# CW521_BallisticGel_Connectors.net
KiCad netlist of a schematic drawn in Altium Designer
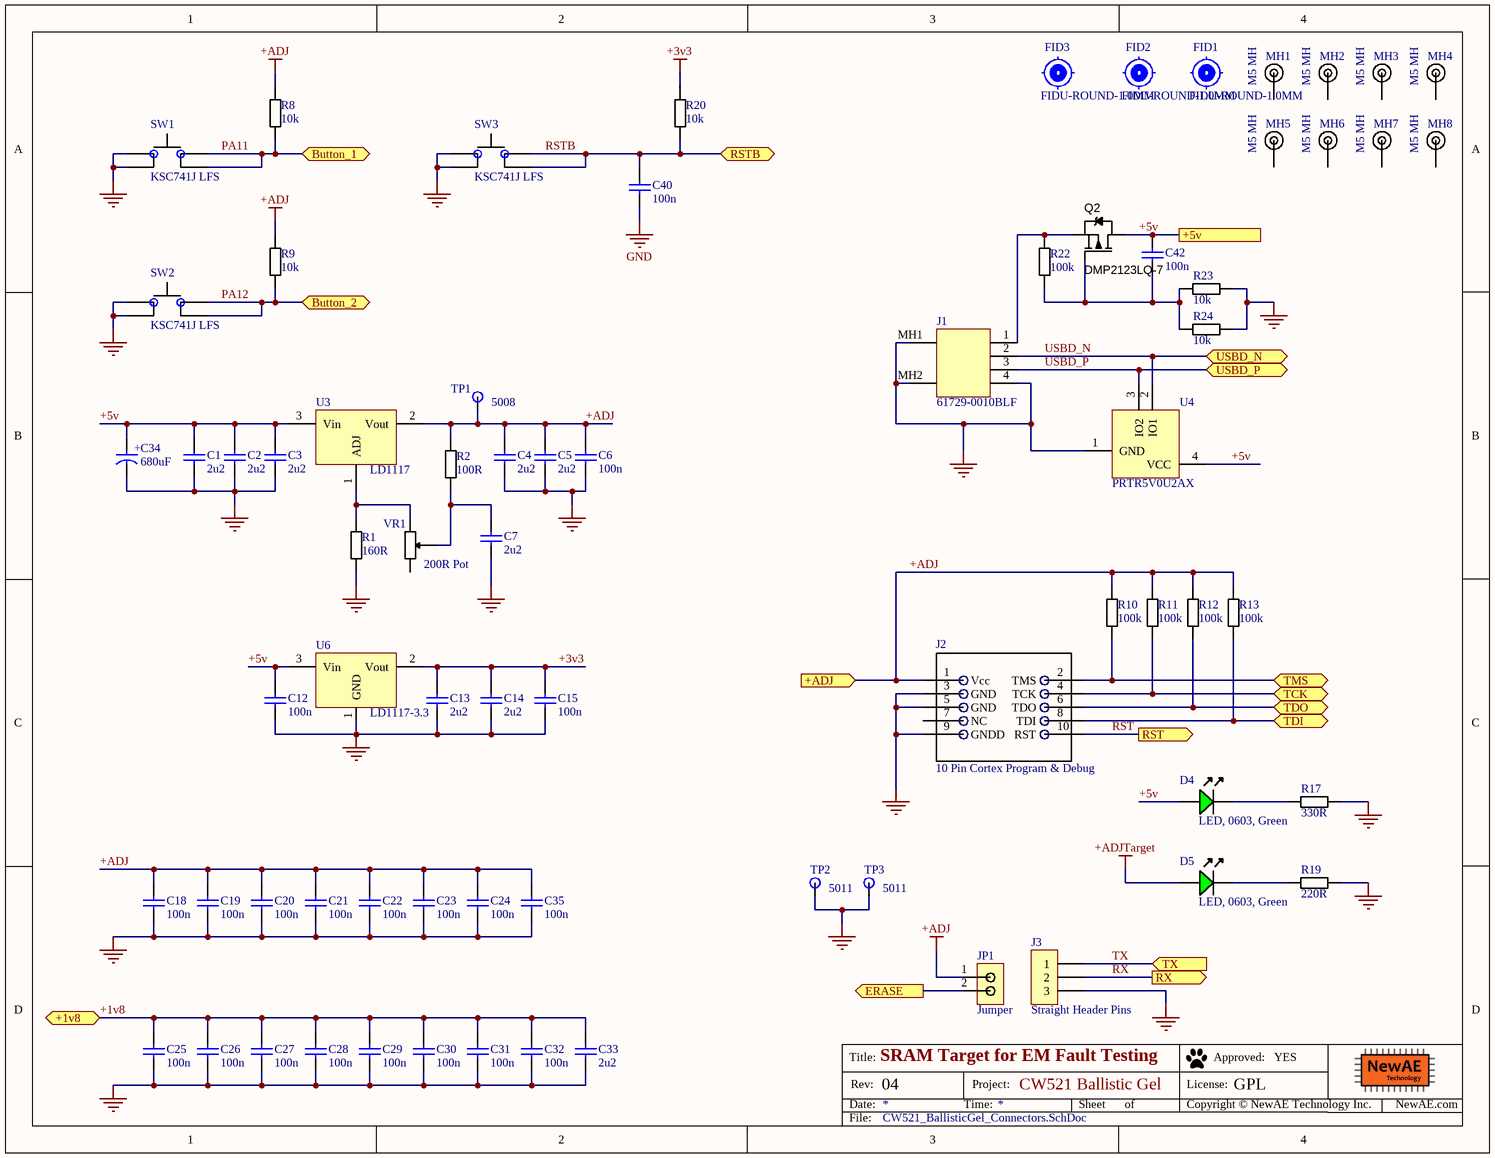
[diagram p0: CW521_BallisticGel_Connectors.SchDoc]

(export (version "E")
  (design (tool "Eeschema 10.0.6"))
  (components
    (comp (ref "C1")
      (value "2u2")
      (footprint "CAPC0603_M")
      (description "2u2, 0603")
      (fields (field (name "PART NUMBER") "CCHIP-2u2-0603"))
      (libsource (lib "NewAE_AltiumLib") (part "CAP"))
    )
    (comp (ref "C2")
      (value "2u2")
      (footprint "CAPC0603_M")
      (description "2u2, 0603")
      (fields (field (name "PART NUMBER") "CCHIP-2u2-0603"))
      (libsource (lib "NewAE_AltiumLib") (part "CAP"))
    )
    (comp (ref "C3")
      (value "2u2")
      (footprint "CAPC0603_M")
      (description "2u2, 0603")
      (fields (field (name "PART NUMBER") "CCHIP-2u2-0603"))
      (libsource (lib "NewAE_AltiumLib") (part "CAP"))
    )
    (comp (ref "C4")
      (value "2u2")
      (footprint "CAPC0603_M")
      (description "2u2, 0603")
      (fields (field (name "PART NUMBER") "CCHIP-2u2-0603"))
      (libsource (lib "NewAE_AltiumLib") (part "CAP"))
    )
    (comp (ref "C5")
      (value "2u2")
      (footprint "CAPC0603_M")
      (description "2u2, 0603")
      (fields (field (name "PART NUMBER") "CCHIP-2u2-0603"))
      (libsource (lib "NewAE_AltiumLib") (part "CAP"))
    )
    (comp (ref "C6")
      (value "100n")
      (footprint "CAPC0603_M")
      (description "100n, 0603")
      (fields (field (name "PART NUMBER") "CCHIP-100n-0603"))
      (libsource (lib "NewAE_AltiumLib") (part "CAP"))
    )
    (comp (ref "C7")
      (value "2u2")
      (footprint "CAPC0603_M")
      (description "2u2, 0603")
      (fields (field (name "PART NUMBER") "CCHIP-2u2-0603"))
      (libsource (lib "NewAE_AltiumLib") (part "CAP"))
    )
    (comp (ref "C12")
      (value "100n")
      (footprint "CAPC0603_M")
      (description "100n, 0603")
      (fields (field (name "PART NUMBER") "CCHIP-100n-0603"))
      (libsource (lib "NewAE_AltiumLib") (part "CAP"))
    )
    (comp (ref "C13")
      (value "2u2")
      (footprint "CAPC0603_M")
      (description "2u2, 0603")
      (fields (field (name "PART NUMBER") "CCHIP-2u2-0603"))
      (libsource (lib "NewAE_AltiumLib") (part "CAP"))
    )
    (comp (ref "C14")
      (value "2u2")
      (footprint "CAPC0603_M")
      (description "2u2, 0603")
      (fields (field (name "PART NUMBER") "CCHIP-2u2-0603"))
      (libsource (lib "NewAE_AltiumLib") (part "CAP"))
    )
    (comp (ref "C15")
      (value "100n")
      (footprint "CAPC0603_M")
      (description "100n, 0603")
      (fields (field (name "PART NUMBER") "CCHIP-100n-0603"))
      (libsource (lib "NewAE_AltiumLib") (part "CAP"))
    )
    (comp (ref "C18")
      (value "100n")
      (footprint "CAPC0603_M")
      (description "100n, 0603")
      (fields (field (name "PART NUMBER") "CCHIP-100n-0603"))
      (libsource (lib "NewAE_AltiumLib") (part "CAP"))
    )
    (comp (ref "C19")
      (value "100n")
      (footprint "CAPC0603_M")
      (description "100n, 0603")
      (fields (field (name "PART NUMBER") "CCHIP-100n-0603"))
      (libsource (lib "NewAE_AltiumLib") (part "CAP"))
    )
    (comp (ref "C20")
      (value "100n")
      (footprint "CAPC0603_M")
      (description "100n, 0603")
      (fields (field (name "PART NUMBER") "CCHIP-100n-0603"))
      (libsource (lib "NewAE_AltiumLib") (part "CAP"))
    )
    (comp (ref "C21")
      (value "100n")
      (footprint "CAPC0603_M")
      (description "100n, 0603")
      (fields (field (name "PART NUMBER") "CCHIP-100n-0603"))
      (libsource (lib "NewAE_AltiumLib") (part "CAP"))
    )
    (comp (ref "C22")
      (value "100n")
      (footprint "CAPC0603_M")
      (description "100n, 0603")
      (fields (field (name "PART NUMBER") "CCHIP-100n-0603"))
      (libsource (lib "NewAE_AltiumLib") (part "CAP"))
    )
    (comp (ref "C23")
      (value "100n")
      (footprint "CAPC0603_M")
      (description "100n, 0603")
      (fields (field (name "PART NUMBER") "CCHIP-100n-0603"))
      (libsource (lib "NewAE_AltiumLib") (part "CAP"))
    )
    (comp (ref "C24")
      (value "100n")
      (footprint "CAPC0603_M")
      (description "100n, 0603")
      (fields (field (name "PART NUMBER") "CCHIP-100n-0603"))
      (libsource (lib "NewAE_AltiumLib") (part "CAP"))
    )
    (comp (ref "C25")
      (value "100n")
      (footprint "CAPC0603_M")
      (description "100n, 0603")
      (fields (field (name "PART NUMBER") "CCHIP-100n-0603"))
      (libsource (lib "NewAE_AltiumLib") (part "CAP"))
    )
    (comp (ref "C26")
      (value "100n")
      (footprint "CAPC0603_M")
      (description "100n, 0603")
      (fields (field (name "PART NUMBER") "CCHIP-100n-0603"))
      (libsource (lib "NewAE_AltiumLib") (part "CAP"))
    )
    (comp (ref "C27")
      (value "100n")
      (footprint "CAPC0603_M")
      (description "100n, 0603")
      (fields (field (name "PART NUMBER") "CCHIP-100n-0603"))
      (libsource (lib "NewAE_AltiumLib") (part "CAP"))
    )
    (comp (ref "C28")
      (value "100n")
      (footprint "CAPC0603_M")
      (description "100n, 0603")
      (fields (field (name "PART NUMBER") "CCHIP-100n-0603"))
      (libsource (lib "NewAE_AltiumLib") (part "CAP"))
    )
    (comp (ref "C29")
      (value "100n")
      (footprint "CAPC0603_M")
      (description "100n, 0603")
      (fields (field (name "PART NUMBER") "CCHIP-100n-0603"))
      (libsource (lib "NewAE_AltiumLib") (part "CAP"))
    )
    (comp (ref "C30")
      (value "100n")
      (footprint "CAPC0603_M")
      (description "100n, 0603")
      (fields (field (name "PART NUMBER") "CCHIP-100n-0603"))
      (libsource (lib "NewAE_AltiumLib") (part "CAP"))
    )
    (comp (ref "C31")
      (value "100n")
      (footprint "CAPC0603_M")
      (description "100n, 0603")
      (fields (field (name "PART NUMBER") "CCHIP-100n-0603"))
      (libsource (lib "NewAE_AltiumLib") (part "CAP"))
    )
    (comp (ref "C32")
      (value "100n")
      (footprint "CAPC0603_M")
      (description "100n, 0603")
      (fields (field (name "PART NUMBER") "CCHIP-100n-0603"))
      (libsource (lib "NewAE_AltiumLib") (part "CAP"))
    )
    (comp (ref "C33")
      (value "2u2")
      (footprint "CAPC0603_M")
      (description "2u2, 0603")
      (fields (field (name "PART NUMBER") "CCHIP-2u2-0603"))
      (libsource (lib "NewAE_AltiumLib") (part "CAP"))
    )
    (comp (ref "C34")
      (value "680uF")
      (footprint "Cap_16v_680uF")
      (description "Aluminum electrolytic 680uF, 8x16mm, radial")
      (fields (field (name "PART NUMBER") "Cap_16v_680uF"))
      (libsource (lib "NewAE_AltiumLib") (part "CAP_POL"))
    )
    (comp (ref "C35")
      (value "100n")
      (footprint "CAPC0603_M")
      (description "100n, 0603")
      (fields (field (name "PART NUMBER") "CCHIP-100n-0603"))
      (libsource (lib "NewAE_AltiumLib") (part "CAP"))
    )
    (comp (ref "C40")
      (value "100n")
      (footprint "CAPC0603_M")
      (description "100n, 0603")
      (fields (field (name "PART NUMBER") "CCHIP-100n-0603"))
      (libsource (lib "NewAE_AltiumLib") (part "CAP"))
    )
    (comp (ref "C42")
      (value "100n")
      (footprint "CAPC0603_M")
      (description "100n, 0603")
      (fields (field (name "PART NUMBER") "CCHIP-100n-0603"))
      (libsource (lib "NewAE_AltiumLib") (part "CAP"))
    )
    (comp (ref "D4")
      (value "LED, 0603, Green")
      (footprint "LED-0603-GREEN")
      (description "Chip LED, Green")
      (fields (field (name "PART NUMBER") "LEDCHIP_0603_GREEN"))
      (libsource (lib "NewAE_AltiumLib") (part "LED_GREEN"))
    )
    (comp (ref "D5")
      (value "LED, 0603, Green")
      (footprint "LED-0603-GREEN")
      (description "Chip LED, Green")
      (fields (field (name "PART NUMBER") "LEDCHIP_0603_GREEN"))
      (libsource (lib "NewAE_AltiumLib") (part "LED_GREEN"))
    )
    (comp (ref "FID1")
      (value "FIDU-ROUND-1.0MM")
      (footprint "FIDU-ROUND-1.0mm")
      (description "ROUND FIDUCIAL")
      (libsource (lib "NewAE_AltiumLib") (part "FIDU-ROUND-1.0MM"))
    )
    (comp (ref "FID2")
      (value "FIDU-ROUND-1.0MM")
      (footprint "FIDU-ROUND-1.0mm")
      (description "ROUND FIDUCIAL")
      (libsource (lib "NewAE_AltiumLib") (part "FIDU-ROUND-1.0MM"))
    )
    (comp (ref "FID3")
      (value "FIDU-ROUND-1.0MM")
      (footprint "FIDU-ROUND-1.0mm")
      (description "ROUND FIDUCIAL")
      (libsource (lib "NewAE_AltiumLib") (part "FIDU-ROUND-1.0MM"))
    )
    (comp (ref "J1")
      (value "61729-0010BLF")
      (footprint "FCI-61729-0010BLF-6_V")
      (description "Single USB 2.0, B Type, Right Angle Jack, Through Hole, RoHS, Tube")
      (fields (field (name "MANUFACTURER") "FCI Electronics"))
      (libsource (lib "Altium Content Vault") (part "CMP-0397-00002-2"))
    )
    (comp (ref "J2")
      (value "10 Pin Cortex Program & Debug")
      (footprint "0.5mm_SMD_Header_5x2")
      (description "10 Pin Cortex Program & Debug 0.5mm pitch")
      (fields (field (name "PART NUMBER") "Cortex_Debug_Header_10Pin"))
      (libsource (lib "NewAE_AltiumLib") (part "Cortex_Debug_Header_10Pin"))
    )
    (comp (ref "J3")
      (value "Straight Header Pins")
      (footprint "1x3_Straight_pins")
      (description "1x3 Straight pin header")
      (fields (field (name "PART NUMBER") "HDR_3PIN"))
      (libsource (lib "NewAE_AltiumLib") (part "1x3_Pin_Header"))
    )
    (comp (ref "JP1")
      (value "Jumper")
      (footprint "2x2.54mm_Header")
      (description "1x2 2.54mm header, male pins")
      (fields (field (name "PART NUMBER") "2_PIN_JUMPER"))
      (libsource (lib "NewAE_AltiumLib") (part "1x2_Pin_Header"))
    )
    (comp (ref "MH1")
      (value "M5 MH")
      (footprint "M5_MOUNTING_HOLE")
      (description "Machine screw #5 plated mounting hole")
      (fields (field (name "PART NUMBER") "M5_Mounting_Hole"))
      (libsource (lib "NewAE_AltiumLib") (part "Mounting_Hole"))
    )
    (comp (ref "MH2")
      (value "M5 MH")
      (footprint "M5_MOUNTING_HOLE")
      (description "Machine screw #5 plated mounting hole")
      (fields (field (name "PART NUMBER") "M5_Mounting_Hole"))
      (libsource (lib "NewAE_AltiumLib") (part "Mounting_Hole"))
    )
    (comp (ref "MH3")
      (value "M5 MH")
      (footprint "M5_MOUNTING_HOLE")
      (description "Machine screw #5 plated mounting hole")
      (fields (field (name "PART NUMBER") "M5_Mounting_Hole"))
      (libsource (lib "NewAE_AltiumLib") (part "Mounting_Hole"))
    )
    (comp (ref "MH4")
      (value "M5 MH")
      (footprint "M5_MOUNTING_HOLE")
      (description "Machine screw #5 plated mounting hole")
      (fields (field (name "PART NUMBER") "M5_Mounting_Hole"))
      (libsource (lib "NewAE_AltiumLib") (part "Mounting_Hole"))
    )
    (comp (ref "MH5")
      (value "M5 MH")
      (footprint "M5_MOUNTING_HOLE")
      (description "Machine screw #5 plated mounting hole")
      (fields (field (name "PART NUMBER") "M5_Mounting_Hole"))
      (libsource (lib "NewAE_AltiumLib") (part "Mounting_Hole"))
    )
    (comp (ref "MH6")
      (value "M5 MH")
      (footprint "M5_MOUNTING_HOLE")
      (description "Machine screw #5 plated mounting hole")
      (fields (field (name "PART NUMBER") "M5_Mounting_Hole"))
      (libsource (lib "NewAE_AltiumLib") (part "Mounting_Hole"))
    )
    (comp (ref "MH7")
      (value "M5 MH")
      (footprint "M5_MOUNTING_HOLE")
      (description "Machine screw #5 plated mounting hole")
      (fields (field (name "PART NUMBER") "M5_Mounting_Hole"))
      (libsource (lib "NewAE_AltiumLib") (part "Mounting_Hole"))
    )
    (comp (ref "MH8")
      (value "M5 MH")
      (footprint "M5_MOUNTING_HOLE")
      (description "Machine screw #5 plated mounting hole")
      (fields (field (name "PART NUMBER") "M5_Mounting_Hole"))
      (libsource (lib "NewAE_AltiumLib") (part "Mounting_Hole"))
    )
    (comp (ref "Q2")
      (value "DMP2123LQ-7")
      (footprint "SOT95P245X110-3M")
      (description "P-Channel, 3A, Logic Level")
      (libsource (lib "NewAE_AltiumLib") (part "MOSFET_P_GSD"))
    )
    (comp (ref "R1")
      (value "160R")
      (footprint "RESC1608X55N")
      (description "160R res, 0603, 1%, 1/10W")
      (fields (field (name "PART NUMBER") "RCHIP-160R-0603") (field (name "TOLERANCE") "1%"))
      (libsource (lib "NewAE_AltiumLib") (part "RES-EU"))
    )
    (comp (ref "R2")
      (value "100R")
      (footprint "RESC1608X55N")
      (description "100R res, 0603, 1%, 1/10W")
      (fields (field (name "PART NUMBER") "RCHIP-100R-0603") (field (name "TOLERANCE") "1%"))
      (libsource (lib "NewAE_AltiumLib") (part "RES-EU"))
    )
    (comp (ref "R8")
      (value "10k")
      (footprint "RESC1608X55N")
      (description "10k res, 0603, 1%, 1/10W")
      (fields (field (name "PART NUMBER") "RCHIP-10K-0603") (field (name "TOLERANCE") "1%"))
      (libsource (lib "NewAE_AltiumLib") (part "RES-EU"))
    )
    (comp (ref "R9")
      (value "10k")
      (footprint "RESC1608X55N")
      (description "10k res, 0603, 1%, 1/10W")
      (fields (field (name "PART NUMBER") "RCHIP-10K-0603") (field (name "TOLERANCE") "1%"))
      (libsource (lib "NewAE_AltiumLib") (part "RES-EU"))
    )
    (comp (ref "R10")
      (value "100k")
      (footprint "RESC1608X55N")
      (description "100k res, 0603, 1%, 1/10W")
      (fields (field (name "PART NUMBER") "RCHIP-100K-0603") (field (name "TOLERANCE") "1%"))
      (libsource (lib "NewAE_AltiumLib") (part "RES-EU"))
    )
    (comp (ref "R11")
      (value "100k")
      (footprint "RESC1608X55N")
      (description "100k res, 0603, 1%, 1/10W")
      (fields (field (name "PART NUMBER") "RCHIP-100K-0603") (field (name "TOLERANCE") "1%"))
      (libsource (lib "NewAE_AltiumLib") (part "RES-EU"))
    )
    (comp (ref "R12")
      (value "100k")
      (footprint "RESC1608X55N")
      (description "100k res, 0603, 1%, 1/10W")
      (fields (field (name "PART NUMBER") "RCHIP-100K-0603") (field (name "TOLERANCE") "1%"))
      (libsource (lib "NewAE_AltiumLib") (part "RES-EU"))
    )
    (comp (ref "R13")
      (value "100k")
      (footprint "RESC1608X55N")
      (description "100k res, 0603, 1%, 1/10W")
      (fields (field (name "PART NUMBER") "RCHIP-100K-0603") (field (name "TOLERANCE") "1%"))
      (libsource (lib "NewAE_AltiumLib") (part "RES-EU"))
    )
    (comp (ref "R17")
      (value "330R")
      (footprint "RESC1608X55N")
      (description "330R res, 0603, 1%, 1/10W")
      (fields (field (name "PART NUMBER") "RCHIP-330R-0603") (field (name "TOLERANCE") "1%"))
      (libsource (lib "") (part "RES-EU_1"))
    )
    (comp (ref "R19")
      (value "220R")
      (footprint "RESC1608X55N")
      (description "220R res, 0603, 1%, 1/10W")
      (fields (field (name "PART NUMBER") "RCHIP-220R-0603") (field (name "TOLERANCE") "1%"))
      (libsource (lib "") (part "RES-EU_1"))
    )
    (comp (ref "R20")
      (value "10k")
      (footprint "RESC1608X55N")
      (description "10k res, 0603, 1%, 1/10W")
      (fields (field (name "PART NUMBER") "RCHIP-10K-0603") (field (name "TOLERANCE") "1%"))
      (libsource (lib "NewAE_AltiumLib") (part "RES-EU"))
    )
    (comp (ref "R22")
      (value "100k")
      (footprint "RESC1608X55N")
      (description "100k res, 0603, 1%, 1/10W")
      (fields (field (name "PART NUMBER") "RCHIP-100K-0603") (field (name "TOLERANCE") "1%"))
      (libsource (lib "NewAE_AltiumLib") (part "RES-EU"))
    )
    (comp (ref "R23")
      (value "10k")
      (footprint "RESC1608X55N")
      (description "10k res, 0603, 1%, 1/10W")
      (fields (field (name "PART NUMBER") "RCHIP-10K-0603") (field (name "TOLERANCE") "1%"))
      (libsource (lib "") (part "RES-EU_1"))
    )
    (comp (ref "R24")
      (value "10k")
      (footprint "RESC1608X55N")
      (description "10k res, 0603, 1%, 1/10W")
      (fields (field (name "PART NUMBER") "RCHIP-10K-0603") (field (name "TOLERANCE") "1%"))
      (libsource (lib "") (part "RES-EU_1"))
    )
    (comp (ref "SW1")
      (value "KSC741J LFS")
      (footprint "CK_KSC7J")
      (description "SWITCH TACTILE SPST-NO 0.01A 32V")
      (fields (field (name "PART NUMBER") "TACTSW-KSC741J"))
      (libsource (lib "NewAE_AltiumLib") (part "SW_PB_NO_4PIN_TACT"))
    )
    (comp (ref "SW2")
      (value "KSC741J LFS")
      (footprint "CK_KSC7J")
      (description "SWITCH TACTILE SPST-NO 0.01A 32V")
      (fields (field (name "PART NUMBER") "TACTSW-KSC741J"))
      (libsource (lib "NewAE_AltiumLib") (part "SW_PB_NO_4PIN_TACT"))
    )
    (comp (ref "SW3")
      (value "KSC741J LFS")
      (footprint "CK_KSC7J")
      (description "SWITCH TACTILE SPST-NO 0.01A 32V")
      (fields (field (name "PART NUMBER") "TACTSW-KSC741J"))
      (libsource (lib "NewAE_AltiumLib") (part "SW_PB_NO_4PIN_TACT"))
    )
    (comp (ref "TP1")
      (value "5008")
      (footprint "KEYSTONE5008")
      (description "TEST POINT PC COMPACT .063\"D ORG")
      (fields (field (name "PART NUMBER") "KEYSTONE_5008"))
      (libsource (lib "NewAE_AltiumLib") (part "KEYSTONE_5008"))
    )
    (comp (ref "TP2")
      (value "5011")
      (footprint "KEYSTONE5011")
      (description "TEST POINT PC MULTI PURPOSE BLK")
      (fields (field (name "PART NUMBER") "KEYSTONE_5011"))
      (libsource (lib "NewAE_AltiumLib") (part "KEYSTONE_5011"))
    )
    (comp (ref "TP3")
      (value "5011")
      (footprint "KEYSTONE5011")
      (description "TEST POINT PC MULTI PURPOSE BLK")
      (fields (field (name "PART NUMBER") "KEYSTONE_5011"))
      (libsource (lib "NewAE_AltiumLib") (part "KEYSTONE_5011"))
    )
    (comp (ref "U3")
      (value "LD1117")
      (footprint "SOT-223")
      (description "IC REG LIN POS ADJ 800MA SOT223")
      (fields (field (name "PART NUMBER") "LD1117SC-R"))
      (libsource (lib "NewAE_AltiumLib") (part "LD1117SC-R"))
    )
    (comp (ref "U4")
      (value "PRTR5V0U2AX")
      (footprint "SOT143B")
      (description "USB 2.0 high-speed ESD")
      (libsource (lib "NewAE_AltiumLib") (part "PRTR5V0U2AX"))
    )
    (comp (ref "U6")
      (value "LD1117-3.3")
      (footprint "SOT-223")
      (description "IC REG LIN POS 3.3V 800MA SOT223")
      (fields (field (name "PART NUMBER") "LD1117S33"))
      (libsource (lib "NewAE_AltiumLib") (part "LD1117S33"))
    )
    (comp (ref "VR1")
      (value "200R Pot")
      (footprint "Pot_TH_upright_3lead")
      (description "200R, 18 turn, 0.5W")
      (fields (field (name "PART NUMBER") "CT94EW201"))
      (libsource (lib "NewAE_AltiumLib") (part "Potentiometer"))
    )
  )
  (nets
    (net (code "1") (name "+3v3") (class "Default")
      (node (ref "C13") (pin "1") (pinfunction "1_1") (pintype "passive"))
      (node (ref "C14") (pin "1") (pinfunction "1_1") (pintype "passive"))
      (node (ref "C15") (pin "1") (pinfunction "1_1") (pintype "passive"))
      (node (ref "R20") (pin "1") (pinfunction "1_1") (pintype "passive"))
      (node (ref "U6") (pin "2") (pinfunction "Vout_2") (pintype "passive"))
    )
    (net (code "2") (name "+ADJ") (class "Default")
      (node (ref "C18") (pin "1") (pinfunction "1_1") (pintype "passive"))
      (node (ref "C19") (pin "1") (pinfunction "1_1") (pintype "passive"))
      (node (ref "C20") (pin "1") (pinfunction "1_1") (pintype "passive"))
      (node (ref "C21") (pin "1") (pinfunction "1_1") (pintype "passive"))
      (node (ref "C22") (pin "1") (pinfunction "1_1") (pintype "passive"))
      (node (ref "C23") (pin "1") (pinfunction "1_1") (pintype "passive"))
      (node (ref "C24") (pin "1") (pinfunction "1_1") (pintype "passive"))
      (node (ref "C35") (pin "1") (pinfunction "1_1") (pintype "passive"))
      (node (ref "C4") (pin "1") (pinfunction "1_1") (pintype "passive"))
      (node (ref "C5") (pin "1") (pinfunction "1_1") (pintype "passive"))
      (node (ref "C6") (pin "1") (pinfunction "1_1") (pintype "passive"))
      (node (ref "J2") (pin "1") (pinfunction "Vcc_1") (pintype "passive"))
      (node (ref "JP1") (pin "1") (pinfunction "1_1") (pintype "passive"))
      (node (ref "R10") (pin "1") (pinfunction "1_1") (pintype "passive"))
      (node (ref "R11") (pin "1") (pinfunction "1_1") (pintype "passive"))
      (node (ref "R12") (pin "1") (pinfunction "1_1") (pintype "passive"))
      (node (ref "R13") (pin "1") (pinfunction "1_1") (pintype "passive"))
      (node (ref "R2") (pin "1") (pinfunction "1_1") (pintype "passive"))
      (node (ref "R8") (pin "1") (pinfunction "1_1") (pintype "passive"))
      (node (ref "R9") (pin "1") (pinfunction "1_1") (pintype "passive"))
      (node (ref "TP1") (pin "1") (pinfunction "1_1") (pintype "passive"))
      (node (ref "U3") (pin "2") (pinfunction "Vout_2") (pintype "passive"))
    )
    (net (code "3") (name "+ADJTarget") (class "Default")
      (node (ref "D5") (pin "A") (pinfunction "A_A") (pintype "passive"))
    )
    (net (code "4") (name "/+1v8") (class "Default")
      (node (ref "C25") (pin "1") (pinfunction "1_1") (pintype "passive"))
      (node (ref "C26") (pin "1") (pinfunction "1_1") (pintype "passive"))
      (node (ref "C27") (pin "1") (pinfunction "1_1") (pintype "passive"))
      (node (ref "C28") (pin "1") (pinfunction "1_1") (pintype "passive"))
      (node (ref "C29") (pin "1") (pinfunction "1_1") (pintype "passive"))
      (node (ref "C30") (pin "1") (pinfunction "1_1") (pintype "passive"))
      (node (ref "C31") (pin "1") (pinfunction "1_1") (pintype "passive"))
      (node (ref "C32") (pin "1") (pinfunction "1_1") (pintype "passive"))
      (node (ref "C33") (pin "1") (pinfunction "1_1") (pintype "passive"))
    )
    (net (code "5") (name "/+5v") (class "Default")
      (node (ref "C1") (pin "1") (pinfunction "1_1") (pintype "passive"))
      (node (ref "C12") (pin "1") (pinfunction "1_1") (pintype "passive"))
      (node (ref "C2") (pin "1") (pinfunction "1_1") (pintype "passive"))
      (node (ref "C3") (pin "1") (pinfunction "1_1") (pintype "passive"))
      (node (ref "C34") (pin "1") (pinfunction "1_1") (pintype "passive"))
      (node (ref "C42") (pin "1") (pinfunction "1_1") (pintype "passive"))
      (node (ref "D4") (pin "A") (pinfunction "A_A") (pintype "passive"))
      (node (ref "Q2") (pin "3") (pinfunction "D_3") (pintype "passive"))
      (node (ref "U3") (pin "3") (pinfunction "Vin_3") (pintype "passive"))
      (node (ref "U4") (pin "4") (pinfunction "VCC_4") (pintype "power_in"))
      (node (ref "U6") (pin "3") (pinfunction "Vin_3") (pintype "passive"))
    )
    (net (code "6") (name "/ERASE") (class "Default")
      (node (ref "JP1") (pin "2") (pinfunction "2_2") (pintype "passive"))
    )
    (net (code "7") (name "/PA11") (class "Default")
      (node (ref "R8") (pin "2") (pinfunction "2_2") (pintype "passive"))
      (node (ref "SW1") (pin "2") (pinfunction "IN_2") (pintype "passive"))
      (node (ref "SW1") (pin "3") (pinfunction "IN_3") (pintype "passive"))
    )
    (net (code "8") (name "/PA12") (class "Default")
      (node (ref "R9") (pin "2") (pinfunction "2_2") (pintype "passive"))
      (node (ref "SW2") (pin "2") (pinfunction "IN_2") (pintype "passive"))
      (node (ref "SW2") (pin "3") (pinfunction "IN_3") (pintype "passive"))
    )
    (net (code "9") (name "/RST") (class "Default")
      (node (ref "J2") (pin "10") (pinfunction "RST_10") (pintype "passive"))
    )
    (net (code "10") (name "/RSTB") (class "Default")
      (node (ref "C40") (pin "1") (pinfunction "1_1") (pintype "passive"))
      (node (ref "R20") (pin "2") (pinfunction "2_2") (pintype "passive"))
      (node (ref "SW3") (pin "2") (pinfunction "IN_2") (pintype "passive"))
      (node (ref "SW3") (pin "3") (pinfunction "IN_3") (pintype "passive"))
    )
    (net (code "11") (name "/RX") (class "Default")
      (node (ref "J3") (pin "2") (pinfunction "2_2") (pintype "passive"))
    )
    (net (code "12") (name "/TCK") (class "Default")
      (node (ref "J2") (pin "4") (pinfunction "TCK_4") (pintype "passive"))
      (node (ref "R11") (pin "2") (pinfunction "2_2") (pintype "passive"))
    )
    (net (code "13") (name "/TDI") (class "Default")
      (node (ref "J2") (pin "8") (pinfunction "TDI_8") (pintype "passive"))
      (node (ref "R13") (pin "2") (pinfunction "2_2") (pintype "passive"))
    )
    (net (code "14") (name "/TDO") (class "Default")
      (node (ref "J2") (pin "6") (pinfunction "TDO_6") (pintype "passive"))
      (node (ref "R12") (pin "2") (pinfunction "2_2") (pintype "passive"))
    )
    (net (code "15") (name "/TMS") (class "Default")
      (node (ref "J2") (pin "2") (pinfunction "TMS_2") (pintype "passive"))
      (node (ref "R10") (pin "2") (pinfunction "2_2") (pintype "passive"))
    )
    (net (code "16") (name "/TX") (class "Default")
      (node (ref "J3") (pin "1") (pinfunction "1_1") (pintype "passive"))
    )
    (net (code "17") (name "/USBD_N") (class "Default")
      (node (ref "J1") (pin "2") (pinfunction "2_2") (pintype "passive"))
      (node (ref "U4") (pin "2") (pinfunction "IO1_2") (pintype "passive"))
    )
    (net (code "18") (name "/USBD_P") (class "Default")
      (node (ref "J1") (pin "3") (pinfunction "3_3") (pintype "passive"))
      (node (ref "U4") (pin "3") (pinfunction "IO2_3") (pintype "passive"))
    )
    (net (code "19") (name "GND") (class "Default")
      (node (ref "C1") (pin "2") (pinfunction "2_2") (pintype "passive"))
      (node (ref "C12") (pin "2") (pinfunction "2_2") (pintype "passive"))
      (node (ref "C13") (pin "2") (pinfunction "2_2") (pintype "passive"))
      (node (ref "C14") (pin "2") (pinfunction "2_2") (pintype "passive"))
      (node (ref "C15") (pin "2") (pinfunction "2_2") (pintype "passive"))
      (node (ref "C18") (pin "2") (pinfunction "2_2") (pintype "passive"))
      (node (ref "C19") (pin "2") (pinfunction "2_2") (pintype "passive"))
      (node (ref "C2") (pin "2") (pinfunction "2_2") (pintype "passive"))
      (node (ref "C20") (pin "2") (pinfunction "2_2") (pintype "passive"))
      (node (ref "C21") (pin "2") (pinfunction "2_2") (pintype "passive"))
      (node (ref "C22") (pin "2") (pinfunction "2_2") (pintype "passive"))
      (node (ref "C23") (pin "2") (pinfunction "2_2") (pintype "passive"))
      (node (ref "C24") (pin "2") (pinfunction "2_2") (pintype "passive"))
      (node (ref "C25") (pin "2") (pinfunction "2_2") (pintype "passive"))
      (node (ref "C26") (pin "2") (pinfunction "2_2") (pintype "passive"))
      (node (ref "C27") (pin "2") (pinfunction "2_2") (pintype "passive"))
      (node (ref "C28") (pin "2") (pinfunction "2_2") (pintype "passive"))
      (node (ref "C29") (pin "2") (pinfunction "2_2") (pintype "passive"))
      (node (ref "C3") (pin "2") (pinfunction "2_2") (pintype "passive"))
      (node (ref "C30") (pin "2") (pinfunction "2_2") (pintype "passive"))
      (node (ref "C31") (pin "2") (pinfunction "2_2") (pintype "passive"))
      (node (ref "C32") (pin "2") (pinfunction "2_2") (pintype "passive"))
      (node (ref "C33") (pin "2") (pinfunction "2_2") (pintype "passive"))
      (node (ref "C34") (pin "2") (pinfunction "2_2") (pintype "passive"))
      (node (ref "C35") (pin "2") (pinfunction "2_2") (pintype "passive"))
      (node (ref "C4") (pin "2") (pinfunction "2_2") (pintype "passive"))
      (node (ref "C40") (pin "2") (pinfunction "2_2") (pintype "passive"))
      (node (ref "C5") (pin "2") (pinfunction "2_2") (pintype "passive"))
      (node (ref "C6") (pin "2") (pinfunction "2_2") (pintype "passive"))
      (node (ref "C7") (pin "2") (pinfunction "2_2") (pintype "passive"))
      (node (ref "J1") (pin "4") (pinfunction "4_4") (pintype "passive"))
      (node (ref "J1") (pin "MH1") (pinfunction "MH1_MH1") (pintype "passive"))
      (node (ref "J1") (pin "MH2") (pinfunction "MH2_MH2") (pintype "passive"))
      (node (ref "J2") (pin "3") (pinfunction "GND_3") (pintype "passive"))
      (node (ref "J2") (pin "5") (pinfunction "GND_5") (pintype "passive"))
      (node (ref "J2") (pin "9") (pinfunction "GNDD_9") (pintype "passive"))
      (node (ref "J3") (pin "3") (pinfunction "3_3") (pintype "passive"))
      (node (ref "R1") (pin "2") (pinfunction "2_2") (pintype "passive"))
      (node (ref "R17") (pin "2") (pinfunction "2_2") (pintype "passive"))
      (node (ref "R19") (pin "2") (pinfunction "2_2") (pintype "passive"))
      (node (ref "R23") (pin "2") (pinfunction "2_2") (pintype "passive"))
      (node (ref "R24") (pin "2") (pinfunction "2_2") (pintype "passive"))
      (node (ref "SW1") (pin "1") (pinfunction "IN_1") (pintype "passive"))
      (node (ref "SW1") (pin "4") (pinfunction "IN_4") (pintype "passive"))
      (node (ref "SW2") (pin "1") (pinfunction "IN_1") (pintype "passive"))
      (node (ref "SW2") (pin "4") (pinfunction "IN_4") (pintype "passive"))
      (node (ref "SW3") (pin "1") (pinfunction "IN_1") (pintype "passive"))
      (node (ref "SW3") (pin "4") (pinfunction "IN_4") (pintype "passive"))
      (node (ref "TP2") (pin "1") (pinfunction "1_1") (pintype "passive"))
      (node (ref "TP3") (pin "1") (pinfunction "1_1") (pintype "passive"))
      (node (ref "U4") (pin "1") (pinfunction "GND_1") (pintype "power_in"))
      (node (ref "U6") (pin "1") (pinfunction "GND_1") (pintype "passive"))
    )
    (net (code "20") (name "Net-(C7-Pad1)") (class "Default")
      (node (ref "C7") (pin "1") (pinfunction "1_1") (pintype "passive"))
      (node (ref "R2") (pin "2") (pinfunction "2_2") (pintype "passive"))
      (node (ref "VR1") (pin "2") (pinfunction "2_2") (pintype "passive"))
    )
    (net (code "21") (name "Net-(D4-PadK)") (class "Default")
      (node (ref "D4") (pin "K") (pinfunction "K_K") (pintype "passive"))
      (node (ref "R17") (pin "1") (pinfunction "1_1") (pintype "passive"))
    )
    (net (code "22") (name "Net-(D5-PadK)") (class "Default")
      (node (ref "D5") (pin "K") (pinfunction "K_K") (pintype "passive"))
      (node (ref "R19") (pin "1") (pinfunction "1_1") (pintype "passive"))
    )
    (net (code "23") (name "Net-(Q2-G)") (class "Default")
      (node (ref "C42") (pin "2") (pinfunction "2_2") (pintype "passive"))
      (node (ref "Q2") (pin "1") (pinfunction "G_1") (pintype "passive"))
      (node (ref "R22") (pin "2") (pinfunction "2_2") (pintype "passive"))
      (node (ref "R23") (pin "1") (pinfunction "1_1") (pintype "passive"))
      (node (ref "R24") (pin "1") (pinfunction "1_1") (pintype "passive"))
    )
    (net (code "24") (name "Net-(Q2-S)") (class "Default")
      (node (ref "J1") (pin "1") (pinfunction "1_1") (pintype "passive"))
      (node (ref "Q2") (pin "2") (pinfunction "S_2") (pintype "passive"))
      (node (ref "R22") (pin "1") (pinfunction "1_1") (pintype "passive"))
    )
    (net (code "25") (name "Net-(U3-ADJ)") (class "Default")
      (node (ref "R1") (pin "1") (pinfunction "1_1") (pintype "passive"))
      (node (ref "U3") (pin "1") (pinfunction "ADJ_1") (pintype "passive"))
      (node (ref "VR1") (pin "1") (pinfunction "1_1") (pintype "passive"))
    )
    (net (code "26") (name "unconnected-(J2-NC-Pad7)") (class "Default")
      (node (ref "J2") (pin "7") (pinfunction "NC_7") (pintype "passive"))
    )
    (net (code "27") (name "unconnected-(MH1-Pad1)") (class "Default")
      (node (ref "MH1") (pin "1") (pinfunction "1_1") (pintype "passive"))
    )
    (net (code "28") (name "unconnected-(MH2-Pad1)") (class "Default")
      (node (ref "MH2") (pin "1") (pinfunction "1_1") (pintype "passive"))
    )
    (net (code "29") (name "unconnected-(MH3-Pad1)") (class "Default")
      (node (ref "MH3") (pin "1") (pinfunction "1_1") (pintype "passive"))
    )
    (net (code "30") (name "unconnected-(MH4-Pad1)") (class "Default")
      (node (ref "MH4") (pin "1") (pinfunction "1_1") (pintype "passive"))
    )
    (net (code "31") (name "unconnected-(MH5-Pad1)") (class "Default")
      (node (ref "MH5") (pin "1") (pinfunction "1_1") (pintype "passive"))
    )
    (net (code "32") (name "unconnected-(MH6-Pad1)") (class "Default")
      (node (ref "MH6") (pin "1") (pinfunction "1_1") (pintype "passive"))
    )
    (net (code "33") (name "unconnected-(MH7-Pad1)") (class "Default")
      (node (ref "MH7") (pin "1") (pinfunction "1_1") (pintype "passive"))
    )
    (net (code "34") (name "unconnected-(MH8-Pad1)") (class "Default")
      (node (ref "MH8") (pin "1") (pinfunction "1_1") (pintype "passive"))
    )
    (net (code "35") (name "unconnected-(VR1-Pad3)") (class "Default")
      (node (ref "VR1") (pin "3") (pinfunction "3_3") (pintype "passive"))
    )
  )
)
